# lm3410-sepic-flashlight-driver-17mm-mk-1.net
KiCad netlist of a schematic drawn in EAGLE
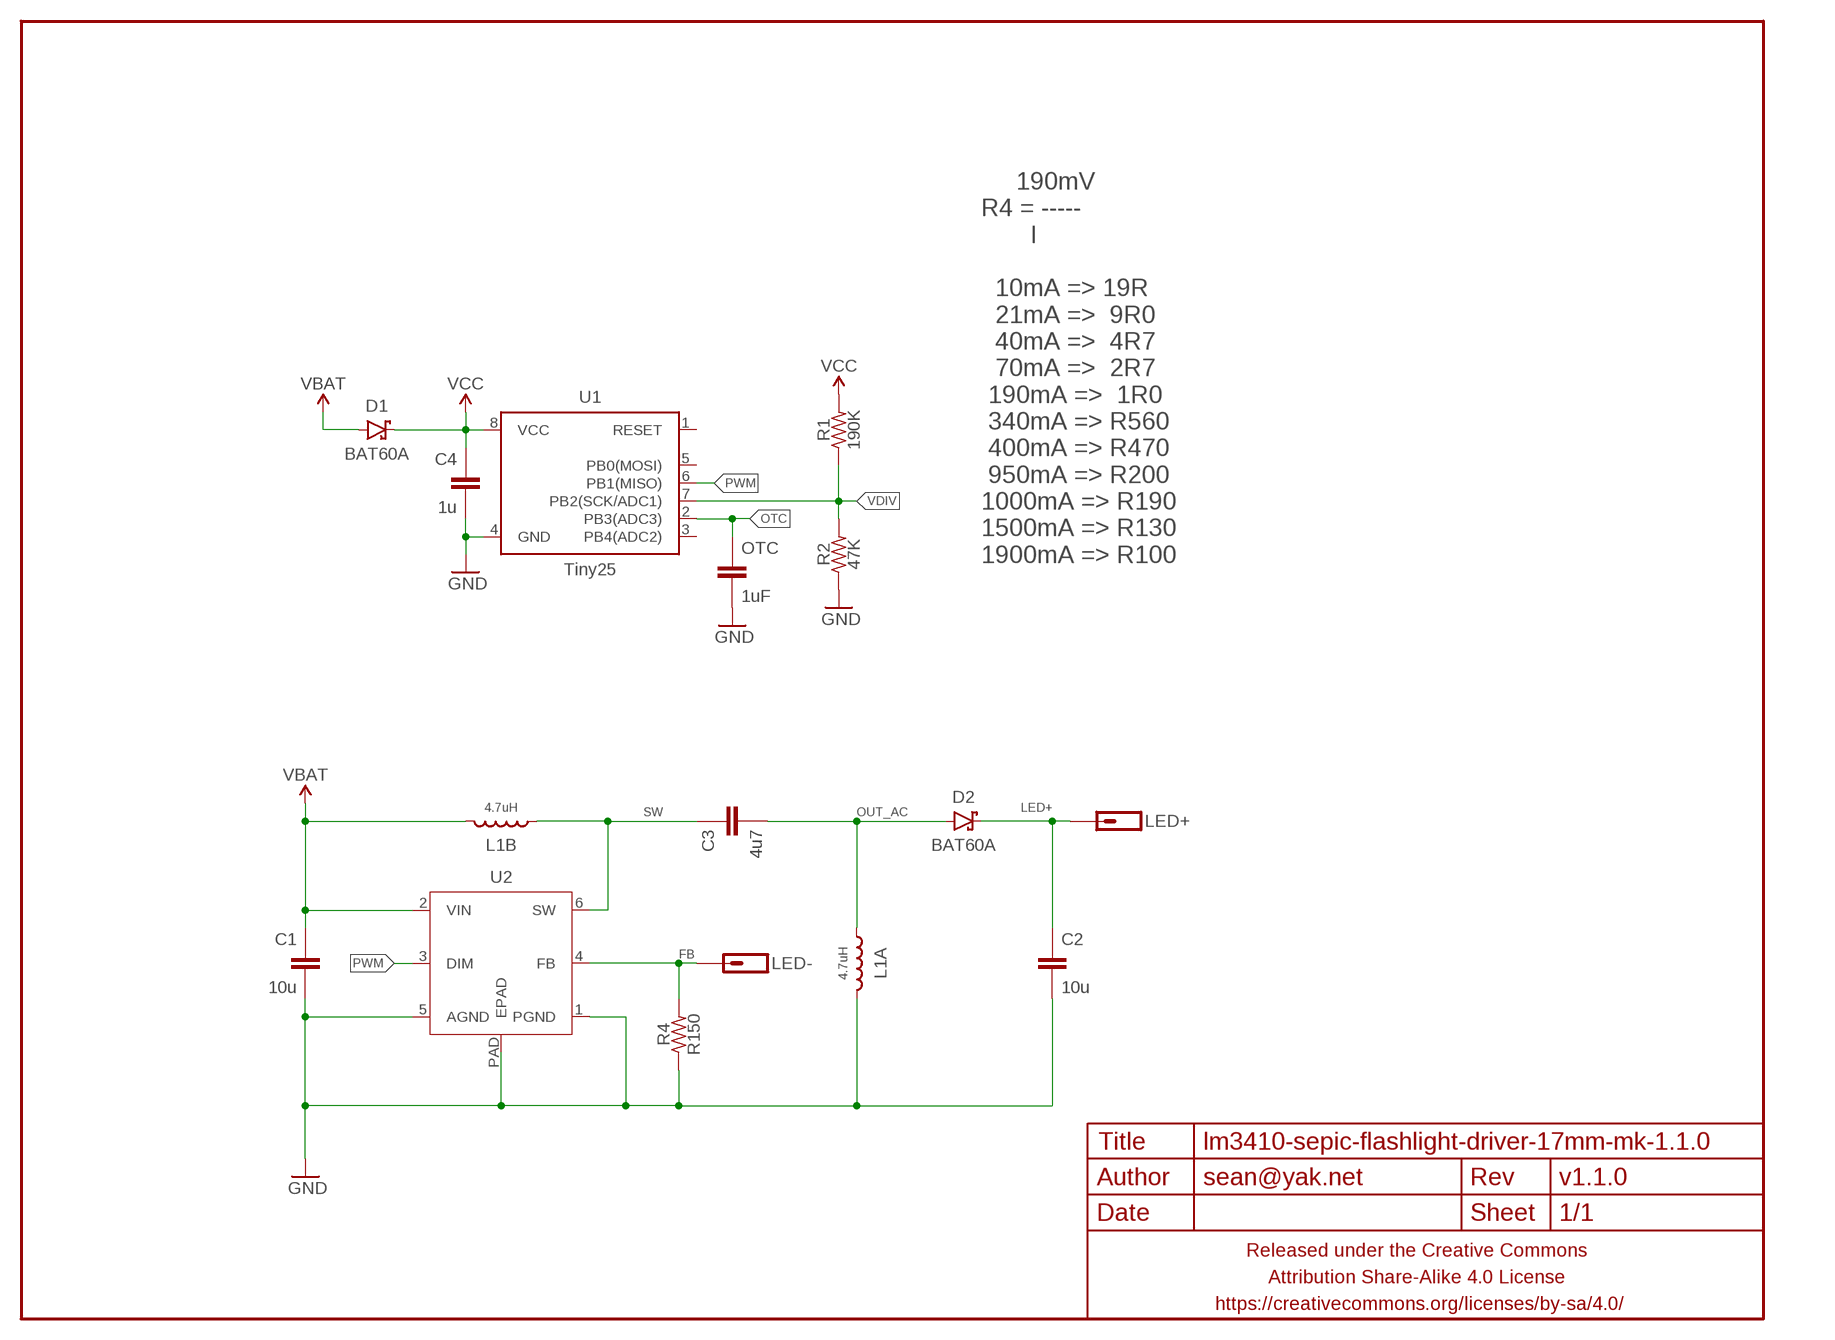
[diagram p0: schematic, sheet 1]

(export (version "E")
  (design (tool "Eeschema 10.0.6"))
  (components
    (comp (ref "C1")
      (value "10u")
      (footprint "eagle-import:C0805-TIGHTER")
      (libsource (lib "eagle-import") (part "CAPACITOR-CERAMICC0805-TIGHTER"))
    )
    (comp (ref "C2")
      (value "10u")
      (footprint "eagle-import:C0805-TIGHTER")
      (libsource (lib "eagle-import") (part "CAPACITOR-CERAMICC0805-TIGHTER"))
    )
    (comp (ref "C3")
      (value "4u7")
      (footprint "eagle-import:C0805-TIGHTER")
      (libsource (lib "eagle-import") (part "CAPACITOR-CERAMICC0805-TIGHTER"))
    )
    (comp (ref "C4")
      (value "1u")
      (footprint "eagle-import:C0402")
      (libsource (lib "eagle-import") (part "CAPACITOR-CERAMICC0402"))
    )
    (comp (ref "D1")
      (value "BAT60A")
      (footprint "eagle-import:SOD323-SCHOTTKY")
      (libsource (lib "eagle-import") (part "DIODE-SCHOTTKYSOD323"))
    )
    (comp (ref "D2")
      (value "BAT60A")
      (footprint "eagle-import:SOD323-SCHOTTKY")
      (libsource (lib "eagle-import") (part "DIODE-SCHOTTKYSOD323"))
    )
    (comp (ref "FRAME1")
      (value "FRAME-LETTERNO_PACKAGE")
      (footprint "eagle-import:DUMMY")
      (fields
        (field (name "DESIGNER") "Nobody")
        (field (name "VERSION") "v01")
        (field (name "DESIGNER_1") "sean@yak.net")
        (field (name "VERSION_1") "v1.1.0")
      )
      (libsource (lib "eagle-import") (part "FRAME-LETTERNO_PACKAGE"))
    )
    (comp (ref "L1")
      (value "4.7uH")
      (footprint "eagle-import:LPD5030-SMALLER-PADS")
      (libsource (lib "eagle-import") (part "INDUCTOR-DUALCOILCRAFT-LPD5030-SMALLER"))
    )
    (comp (ref "LED+")
      (value "M01PTH-1MM-CIR-NS")
      (footprint "eagle-import:1X01-1MM-CIR-NS")
      (libsource (lib "eagle-import") (part "M01PTH-1MM-CIR-NS"))
    )
    (comp (ref "LED-")
      (value "M01PTH-1MM-CIR-NS")
      (footprint "eagle-import:1X01-1MM-CIR-NS")
      (libsource (lib "eagle-import") (part "M01PTH-1MM-CIR-NS"))
    )
    (comp (ref "OTC")
      (value "1uF")
      (footprint "eagle-import:C0402")
      (libsource (lib "eagle-import") (part "CAPACITOR-CERAMICC0402"))
    )
    (comp (ref "R1")
      (value "190K")
      (footprint "eagle-import:R0402")
      (libsource (lib "eagle-import") (part "RESISTORR0402"))
    )
    (comp (ref "R2")
      (value "47K")
      (footprint "eagle-import:R0402")
      (libsource (lib "eagle-import") (part "RESISTORR0402"))
    )
    (comp (ref "R4")
      (value "R150")
      (footprint "eagle-import:R0805-TIGHTER")
      (libsource (lib "eagle-import") (part "RESISTORR0805-TIGHTER"))
    )
    (comp (ref "U1")
      (value "Tiny25")
      (footprint "eagle-import:SO08-SKINNYPADS")
      (libsource (lib "eagle-import") (part "ATTINY45TINY25-SOICN-NARROWER"))
    )
    (comp (ref "U2")
      (value "LM3410XSDNGG")
      (footprint "eagle-import:DFN300X300X80-7N")
      (fields (field (name "MPN") "LM3410XSD"))
      (libsource (lib "eagle-import") (part "LM3410XSDNGG"))
    )
  )
  (nets
    (net (code "1") (name "/FB") (class "Default")
      (node (ref "LED-") (pin "1") (pinfunction "1_1") (pintype "passive"))
      (node (ref "R4") (pin "2") (pinfunction "2_2") (pintype "passive"))
      (node (ref "U2") (pin "4") (pinfunction "FB_4") (pintype "input"))
    )
    (net (code "2") (name "/LED+") (class "Default")
      (node (ref "C2") (pin "1") (pinfunction "1_1") (pintype "passive"))
      (node (ref "D2") (pin "C") (pinfunction "C_C") (pintype "passive"))
      (node (ref "LED+") (pin "1") (pinfunction "1_1") (pintype "passive"))
    )
    (net (code "3") (name "/OUT_AC") (class "Default")
      (node (ref "C3") (pin "2") (pinfunction "2_2") (pintype "passive"))
      (node (ref "D2") (pin "A") (pinfunction "A_A") (pintype "passive"))
      (node (ref "L1") (pin "1") (pinfunction "1_1") (pintype "passive"))
    )
    (net (code "4") (name "/SW") (class "Default")
      (node (ref "C3") (pin "1") (pinfunction "1_1") (pintype "passive"))
      (node (ref "L1") (pin "4") (pinfunction "1_4") (pintype "passive"))
      (node (ref "U2") (pin "6") (pinfunction "SW_6") (pintype "output"))
    )
    (net (code "5") (name "GND") (class "Default")
      (node (ref "C1") (pin "2") (pinfunction "2_2") (pintype "passive"))
      (node (ref "C2") (pin "2") (pinfunction "2_2") (pintype "passive"))
      (node (ref "C4") (pin "2") (pinfunction "2_2") (pintype "passive"))
      (node (ref "L1") (pin "2") (pinfunction "2_2") (pintype "passive"))
      (node (ref "OTC") (pin "2") (pinfunction "2_2") (pintype "passive"))
      (node (ref "R2") (pin "1") (pinfunction "1_1") (pintype "passive"))
      (node (ref "R4") (pin "1") (pinfunction "1_1") (pintype "passive"))
      (node (ref "U1") (pin "4") (pinfunction "GND_4") (pintype "bidirectional"))
      (node (ref "U2") (pin "1") (pinfunction "PGND_1") (pintype "passive"))
      (node (ref "U2") (pin "5") (pinfunction "AGND_5") (pintype "passive"))
      (node (ref "U2") (pin "PAD") (pinfunction "EPAD_PAD") (pintype "passive"))
    )
    (net (code "6") (name "OTC") (class "Default")
      (node (ref "OTC") (pin "1") (pinfunction "1_1") (pintype "passive"))
      (node (ref "U1") (pin "2") (pinfunction "PB3(ADC3)_2") (pintype "bidirectional"))
    )
    (net (code "7") (name "PWM") (class "Default")
      (node (ref "U1") (pin "6") (pinfunction "PB1(MISO)_6") (pintype "bidirectional"))
      (node (ref "U2") (pin "3") (pinfunction "DIM_3") (pintype "input"))
    )
    (net (code "8") (name "VBAT") (class "Default")
      (node (ref "C1") (pin "1") (pinfunction "1_1") (pintype "passive"))
      (node (ref "D1") (pin "A") (pinfunction "A_A") (pintype "passive"))
      (node (ref "L1") (pin "3") (pinfunction "2_3") (pintype "passive"))
      (node (ref "U2") (pin "2") (pinfunction "VIN_2") (pintype "power_in"))
    )
    (net (code "9") (name "VCC") (class "Default")
      (node (ref "C4") (pin "1") (pinfunction "1_1") (pintype "passive"))
      (node (ref "D1") (pin "C") (pinfunction "C_C") (pintype "passive"))
      (node (ref "R1") (pin "2") (pinfunction "2_2") (pintype "passive"))
      (node (ref "U1") (pin "8") (pinfunction "VCC_8") (pintype "bidirectional"))
    )
    (net (code "10") (name "VDIV") (class "Default")
      (node (ref "R1") (pin "1") (pinfunction "1_1") (pintype "passive"))
      (node (ref "R2") (pin "2") (pinfunction "2_2") (pintype "passive"))
      (node (ref "U1") (pin "7") (pinfunction "PB2(SCK/ADC1)_7") (pintype "bidirectional"))
    )
    (net (code "11") (name "unconnected-(U1-PB0(MOSI)-Pad5)") (class "Default")
      (node (ref "U1") (pin "5") (pinfunction "PB0(MOSI)_5") (pintype "bidirectional"))
    )
    (net (code "12") (name "unconnected-(U1-PB4(ADC2)-Pad3)") (class "Default")
      (node (ref "U1") (pin "3") (pinfunction "PB4(ADC2)_3") (pintype "bidirectional"))
    )
    (net (code "13") (name "unconnected-(U1-RESET-Pad1)") (class "Default")
      (node (ref "U1") (pin "1") (pinfunction "RESET_1") (pintype "bidirectional"))
    )
  )
)
